# UVB_Module.net
KiCad netlist of a schematic drawn in EAGLE
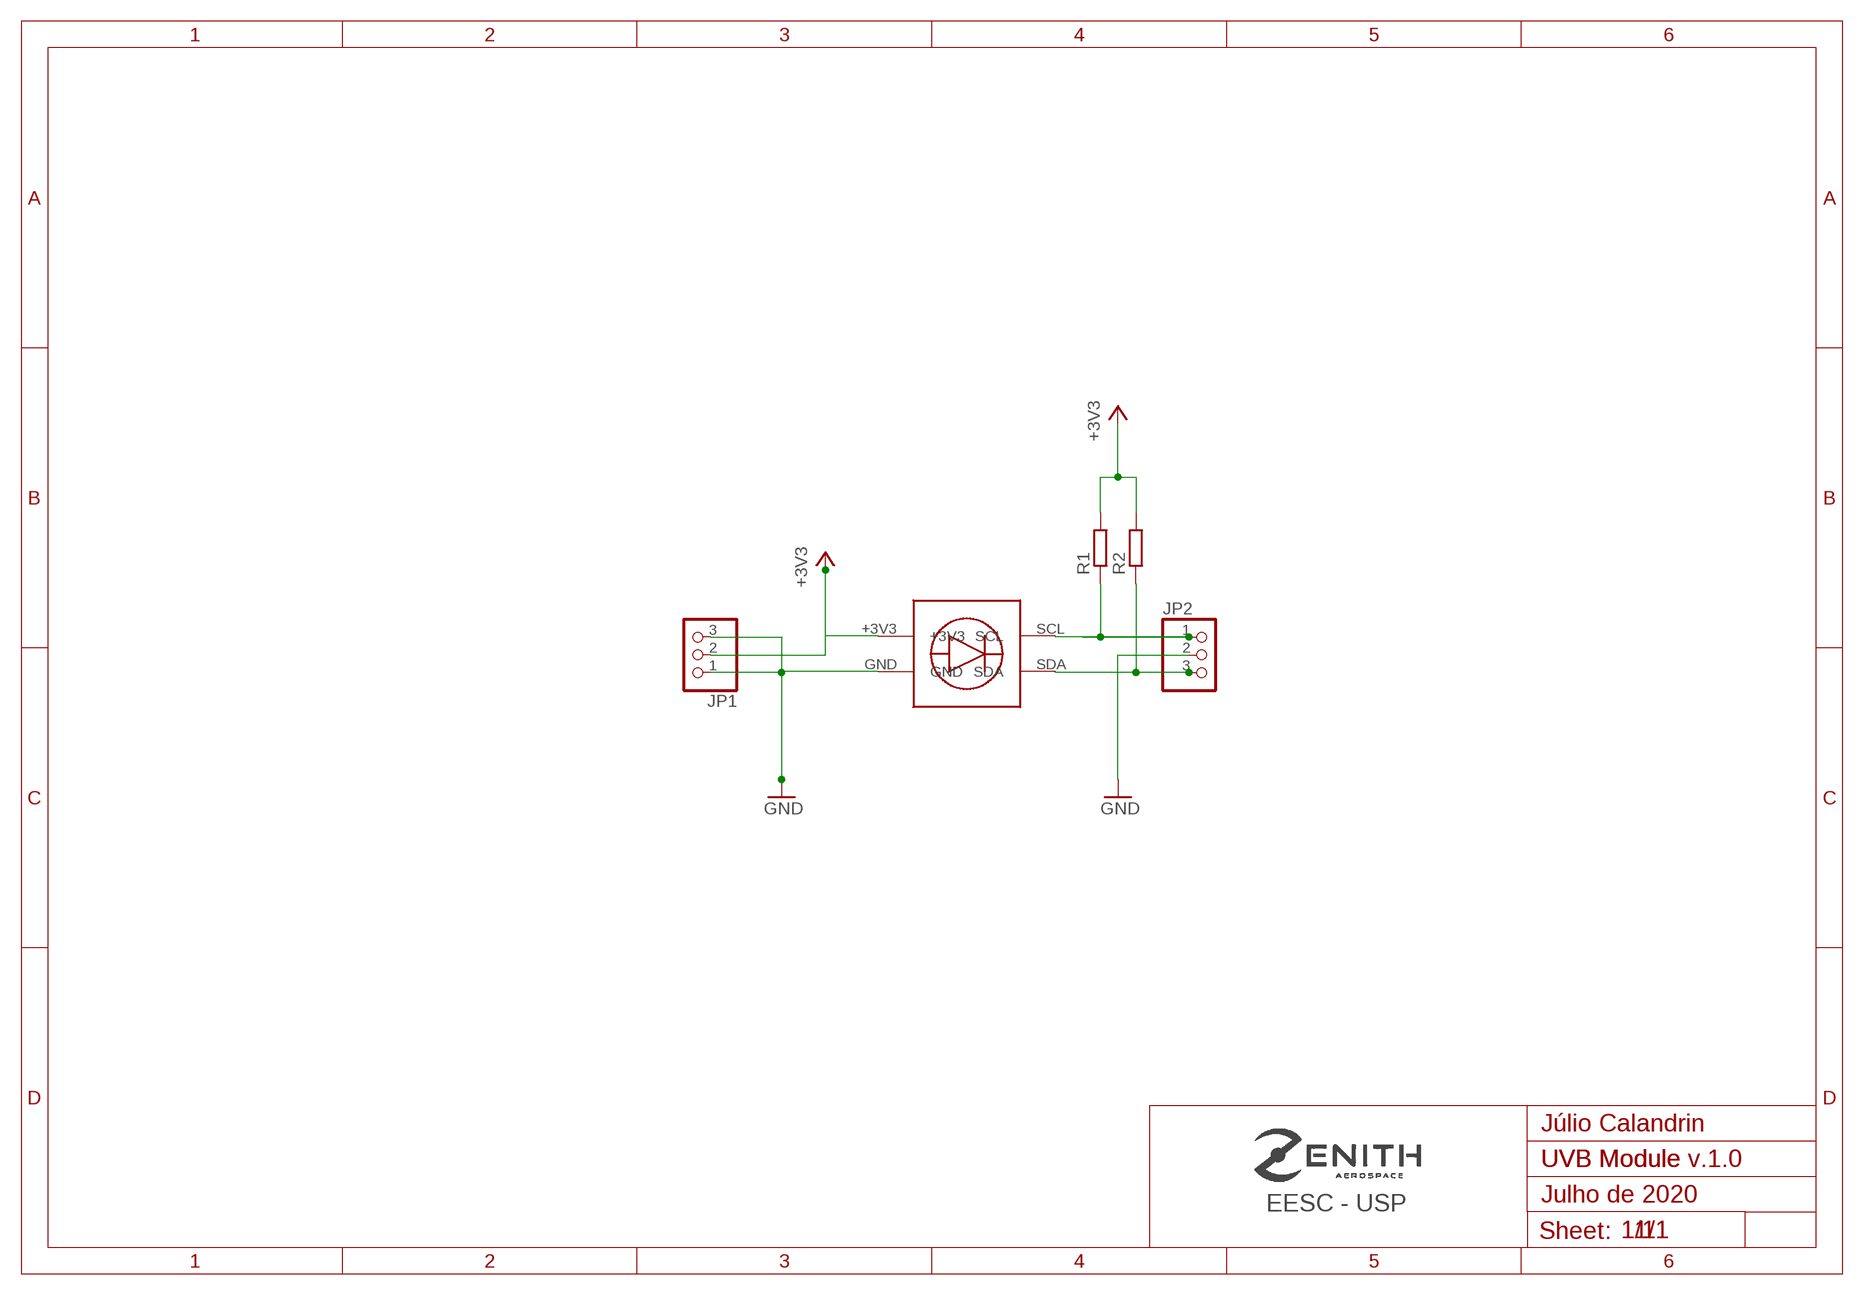
[diagram p0: schematic, sheet 1]

(export (version "E")
  (design (tool "Eeschema 10.0.6"))
  (components
    (comp (ref "JP1")
      (value "PINHD-1X3")
      (footprint "eagle-import:1X03")
      (libsource (lib "eagle-import") (part "PINHD-1X3"))
    )
    (comp (ref "JP2")
      (value "PINHD-1X3")
      (footprint "eagle-import:1X03")
      (libsource (lib "eagle-import") (part "PINHD-1X3"))
    )
    (comp (ref "R1")
      (value "R-EU_R0805")
      (footprint "eagle-import:R0805")
      (libsource (lib "eagle-import") (part "R-EU_R0805"))
    )
    (comp (ref "R2")
      (value "R-EU_R0805")
      (footprint "eagle-import:R0805")
      (libsource (lib "eagle-import") (part "R-EU_R0805"))
    )
    (comp (ref "U$1")
      (value "BREAKOUT_UV-B")
      (footprint "eagle-import:PADS_UV-A_B")
      (libsource (lib "eagle-import") (part "BREAKOUT_UV-B"))
    )
  )
  (nets
    (net (code "1") (name "+3V3") (class "Default")
      (node (ref "JP1") (pin "2") (pinfunction "2_2") (pintype "passive"))
      (node (ref "R1") (pin "2") (pinfunction "2_2") (pintype "passive"))
      (node (ref "R2") (pin "2") (pinfunction "2_2") (pintype "passive"))
      (node (ref "U$1") (pin "+3V3") (pinfunction "+3V3_+3V3") (pintype "bidirectional"))
    )
    (net (code "2") (name "GND") (class "Default")
      (node (ref "JP1") (pin "1") (pinfunction "1_1") (pintype "passive"))
      (node (ref "JP1") (pin "3") (pinfunction "3_3") (pintype "passive"))
      (node (ref "JP2") (pin "2") (pinfunction "2_2") (pintype "passive"))
      (node (ref "U$1") (pin "GND") (pinfunction "GND_GND") (pintype "bidirectional"))
    )
    (net (code "3") (name "Net-(JP2-Pad1)") (class "Default")
      (node (ref "JP2") (pin "1") (pinfunction "1_1") (pintype "passive"))
      (node (ref "R1") (pin "1") (pinfunction "1_1") (pintype "passive"))
      (node (ref "U$1") (pin "SCL") (pinfunction "SCL_SCL") (pintype "bidirectional"))
    )
    (net (code "4") (name "Net-(JP2-Pad3)") (class "Default")
      (node (ref "JP2") (pin "3") (pinfunction "3_3") (pintype "passive"))
      (node (ref "R2") (pin "1") (pinfunction "1_1") (pintype "passive"))
      (node (ref "U$1") (pin "SDA") (pinfunction "SDA_SDA") (pintype "bidirectional"))
    )
  )
)
